# V1_0.net
KiCad netlist of a schematic drawn in Altium Designer
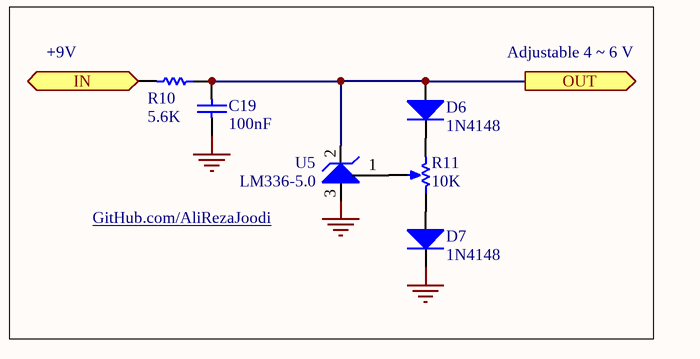
[diagram p0: V1.0.SchDoc]

(export (version "E")
  (design (tool "Eeschema 10.0.6"))
  (components
    (comp (ref "C19")
      (value "100nF")
      (footprint "CAPNTO2.54-3.05x1.78A")
      (description "Capacitor")
      (fields
        (field (name "MANUFACTURER") "Generic Components")
        (field (name "Comment") "Cap")
        (field (name "PUBLISHER") "Altium Limited")
      )
      (libsource (lib "Miscellaneous Devices") (part "Cap"))
    )
    (comp (ref "D6")
      (value "1N4148")
      (footprint "DIODE0.4_Glass")
      (description "Default Diode")
      (fields (field (name "MANUFACTURER") "Generic Components") (field (name "PUBLISHER") "Altium Limited"))
      (libsource (lib "Miscellaneous Devices") (part "Diode"))
    )
    (comp (ref "D7")
      (value "1N4148")
      (footprint "DIODE0.4_Glass")
      (description "Default Diode")
      (fields (field (name "MANUFACTURER") "Generic Components") (field (name "PUBLISHER") "Altium Limited"))
      (libsource (lib "Miscellaneous Devices") (part "Diode"))
    )
    (comp (ref "R10")
      (value "5.6K")
      (footprint "AXIAL-0.4")
      (description "Resistor")
      (fields (field (name "Comment") "Res1") (field (name "PUBLISHER") "Altium Limited"))
      (libsource (lib "Miscellaneous Devices") (part "Res1"))
    )
    (comp (ref "R11")
      (value "10K")
      (footprint "VR4_")
      (description "Potentiometer")
      (fields
        (field (name "MANUFACTURER") "Generic Components")
        (field (name "Comment") "POT")
        (field (name "PUBLISHER") "Altium Limited")
      )
      (libsource (lib "my Libraries") (part "RPot1"))
    )
    (comp (ref "U5")
      (value "LM336-5.0")
      (footprint "TO92C")
      (description "Programmable Shunt Regulator")
      (libsource (lib "my Libraries") (part "LM336"))
    )
  )
  (nets
    (net (code "1") (name "/IN") (class "Default")
      (node (ref "R10") (pin "2") (pinfunction "2_2") (pintype "passive"))
    )
    (net (code "2") (name "/OUT") (class "Default")
      (node (ref "C19") (pin "1") (pinfunction "1_1") (pintype "passive"))
      (node (ref "D6") (pin "1") (pinfunction "A_1") (pintype "passive"))
      (node (ref "R10") (pin "1") (pinfunction "1_1") (pintype "passive"))
      (node (ref "U5") (pin "2") (pinfunction "+_2") (pintype "passive"))
    )
    (net (code "3") (name "GND") (class "Default")
      (node (ref "C19") (pin "2") (pinfunction "2_2") (pintype "passive"))
      (node (ref "D7") (pin "2") (pinfunction "K_2") (pintype "passive"))
      (node (ref "U5") (pin "3") (pinfunction "-_3") (pintype "passive"))
    )
    (net (code "4") (name "Net-(D6-K)") (class "Default")
      (node (ref "D6") (pin "2") (pinfunction "K_2") (pintype "passive"))
      (node (ref "R11") (pin "2") (pinfunction "BOT_2") (pintype "passive"))
    )
    (net (code "5") (name "Net-(D7-A)") (class "Default")
      (node (ref "D7") (pin "1") (pinfunction "A_1") (pintype "passive"))
      (node (ref "R11") (pin "1") (pinfunction "TOP_1") (pintype "passive"))
    )
    (net (code "6") (name "Net-(R11-TAP)") (class "Default")
      (node (ref "R11") (pin "3") (pinfunction "TAP_3") (pintype "passive"))
      (node (ref "U5") (pin "1") (pinfunction "Adj_1") (pintype "passive"))
    )
  )
)
